# SCH_Driver_Key_PCB_3_5_3_8_5_0_2022-10-0.net
KiCad netlist of a schematic drawn in EasyEDA
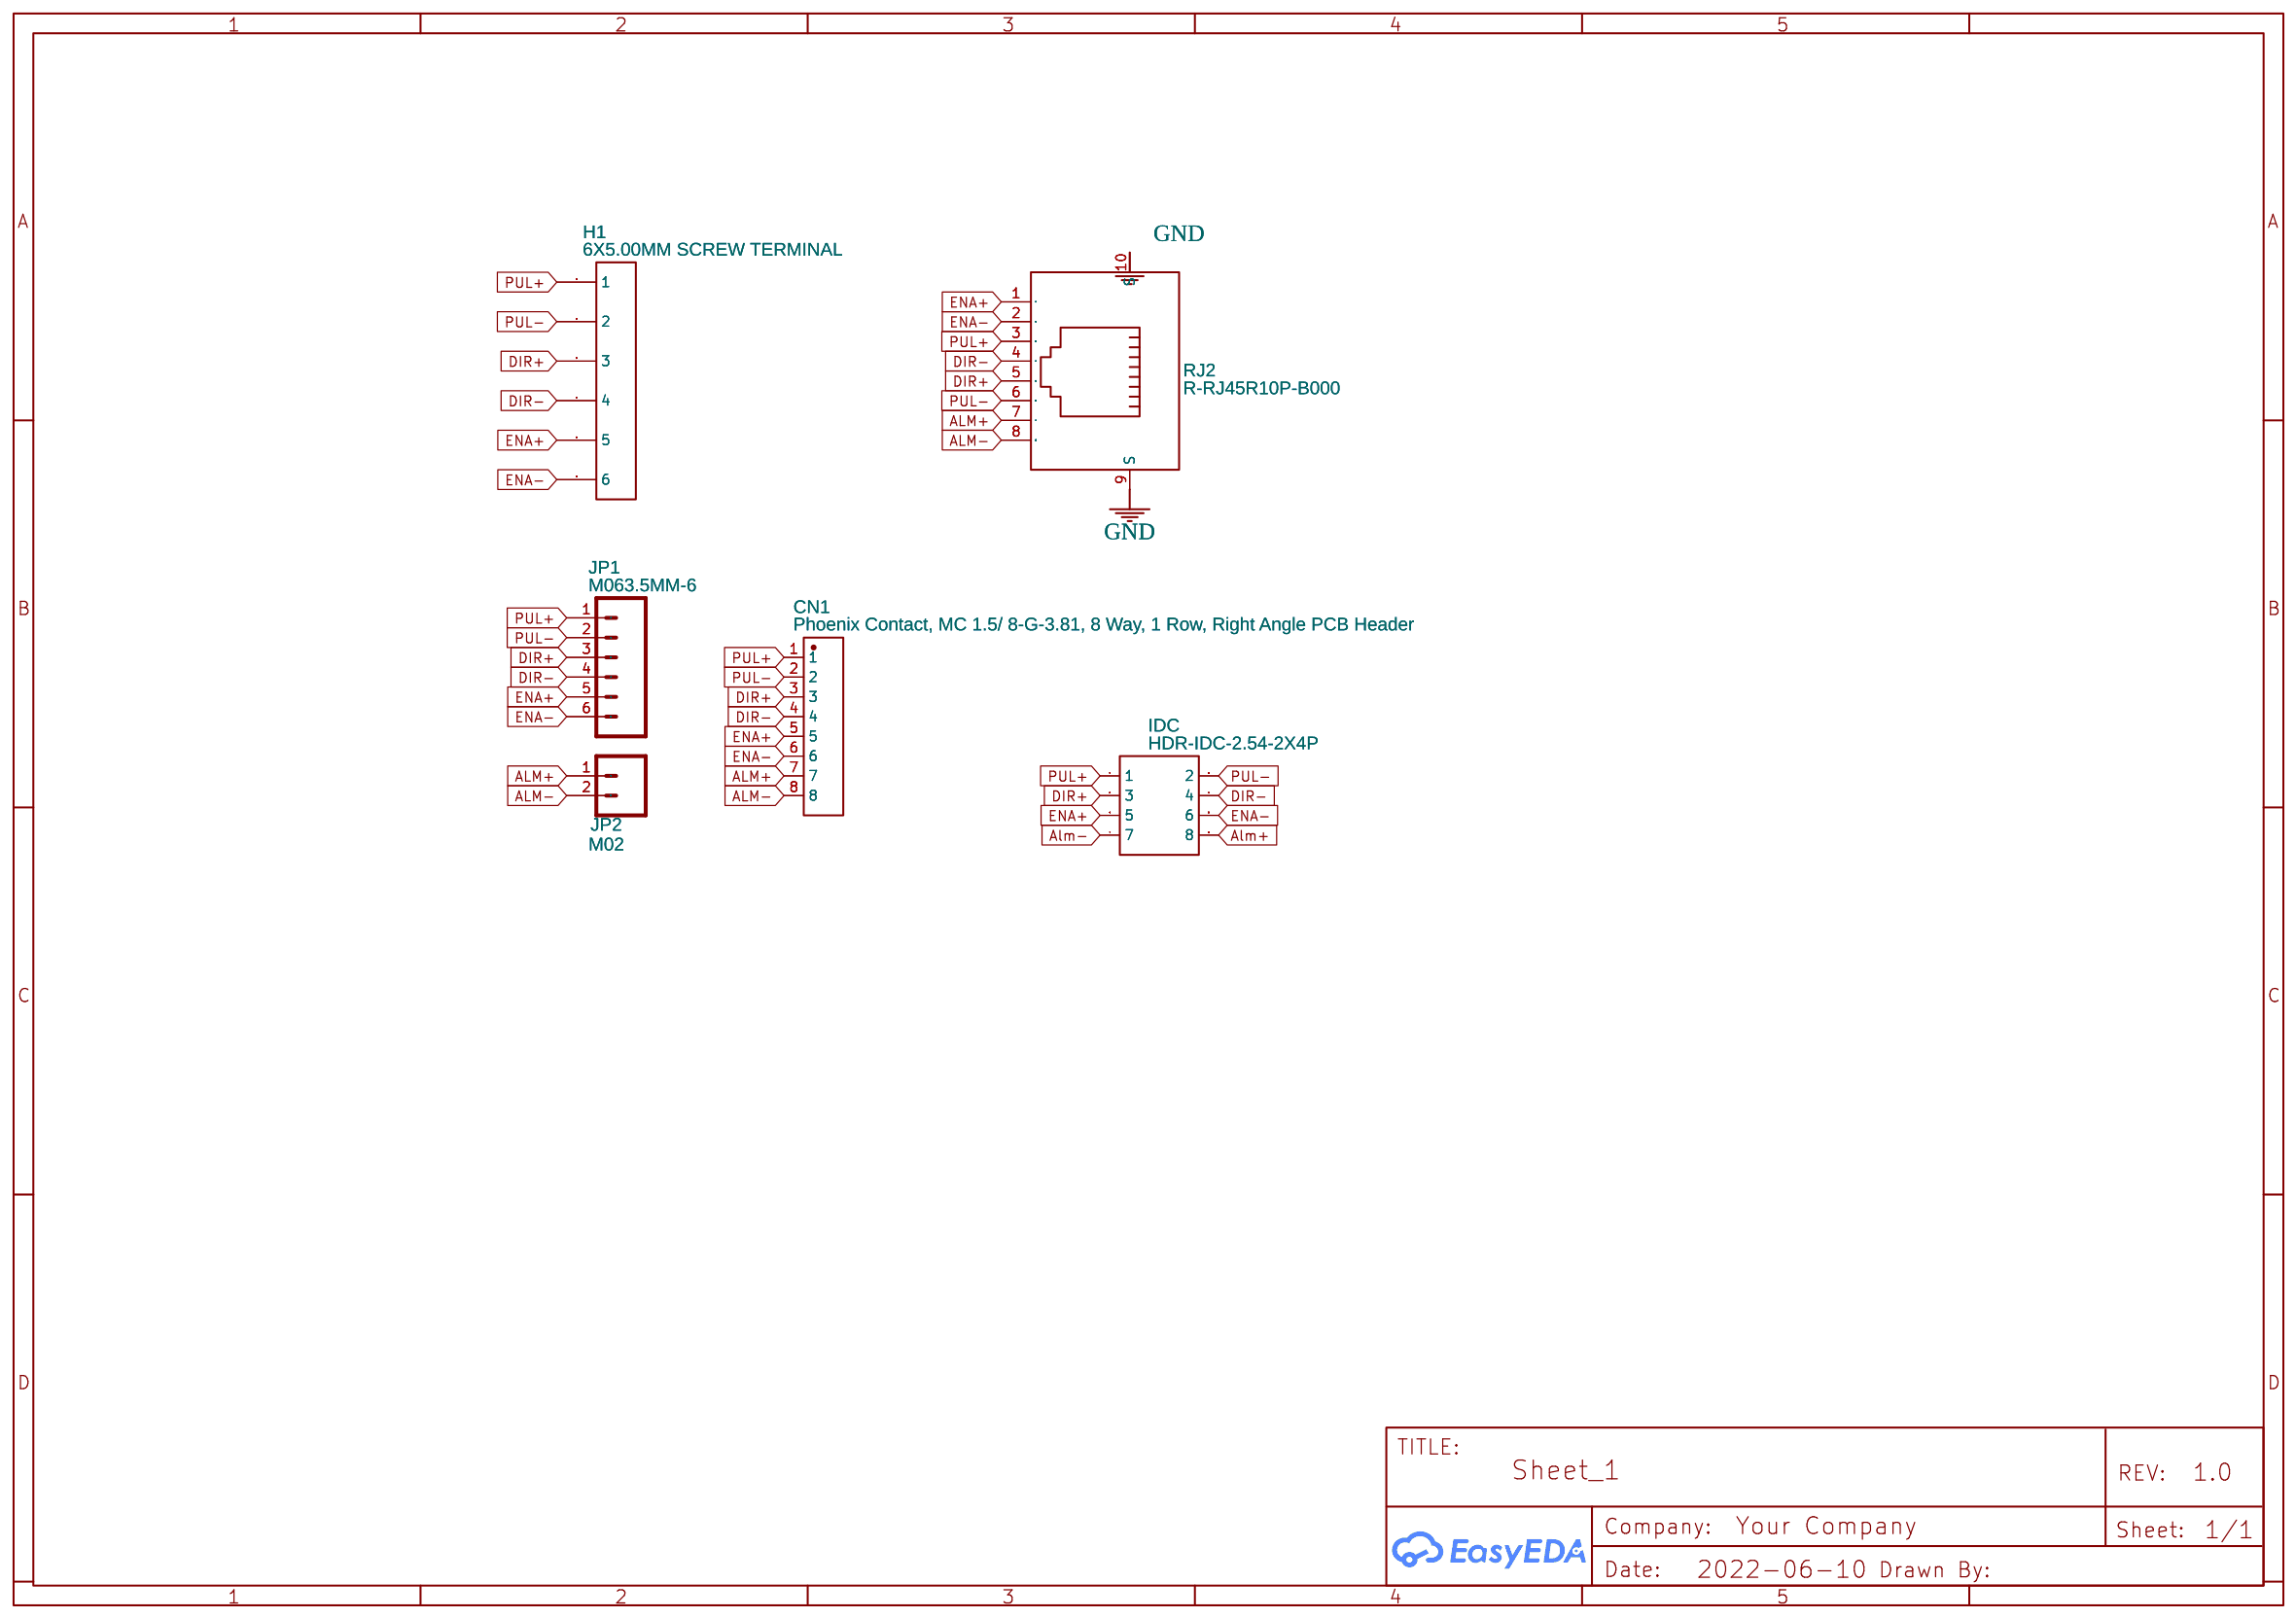
[diagram p0: schematic sheet]

(export (version "E")
  (design (tool "Eeschema 10.0.6"))
  (components
    (comp (ref "CN1")
      (value "Phoenix Contact, MC 1.5/ 8-G-3.81, 8 Way, 1 Row, Right Angle PCB Header")
      (fields (field (name "BOM_Manufacturer Part") "1803332") (field (name "BOM_Supplier Part") "220-4793"))
      (libsource (lib "") (part "Phoenix Contact, MC 1.5/ 8-G-3.81, 8 Way, 1 Row, Right Angle PCB Header"))
    )
    (comp (ref "H1") (value "6X5.00MM SCREW TERMINAL") (libsource (lib "") (part "6X5.00MM SCREW TERMINAL")))
    (comp (ref "IDC")
      (value "HDR-IDC-2.54-2X4P")
      (fields
        (field (name "BOM_Manufacturer Part") "IDC Box 2X4 2.54MM")
        (field (name "BOM_Supplier Part") "C9135")
      )
      (libsource (lib "") (part "HDR-IDC-2.54-2X4P"))
    )
    (comp (ref "JP1") (value "M063.5MM-6") (libsource (lib "") (part "M063.5MM-6")))
    (comp (ref "JP2") (value "M02") (libsource (lib "") (part "M02")))
    (comp (ref "RJ2")
      (value "R-RJ45R10P-B000")
      (fields (field (name "BOM_Supplier Part") "C386758"))
      (libsource (lib "") (part "R-RJ45R10P-B000"))
    )
  )
  (nets
    (net (code "1") (name "ALM+") (class "Default")
      (node (ref "CN1") (pin "7") (pinfunction "7_7") (pintype "unspecified"))
      (node (ref "JP2") (pin "1") (pinfunction "1_1") (pintype "unspecified"))
      (node (ref "RJ2") (pin "7") (pinfunction "7_7") (pintype "unspecified"))
    )
    (net (code "2") (name "ALM-") (class "Default")
      (node (ref "CN1") (pin "8") (pinfunction "8_8") (pintype "unspecified"))
      (node (ref "JP2") (pin "2") (pinfunction "2_2") (pintype "unspecified"))
      (node (ref "RJ2") (pin "8") (pinfunction "8_8") (pintype "unspecified"))
    )
    (net (code "3") (name "Alm+") (class "Default")
      (node (ref "IDC") (pin "8") (pinfunction "8_8") (pintype "unspecified"))
    )
    (net (code "4") (name "Alm-") (class "Default")
      (node (ref "IDC") (pin "7") (pinfunction "7_7") (pintype "unspecified"))
    )
    (net (code "5") (name "DIR+") (class "Default")
      (node (ref "CN1") (pin "3") (pinfunction "3_3") (pintype "unspecified"))
      (node (ref "H1") (pin "3") (pinfunction "3_3") (pintype "unspecified"))
      (node (ref "IDC") (pin "3") (pinfunction "3_3") (pintype "unspecified"))
      (node (ref "JP1") (pin "3") (pinfunction "3_3") (pintype "unspecified"))
      (node (ref "RJ2") (pin "5") (pinfunction "5_5") (pintype "unspecified"))
    )
    (net (code "6") (name "DIR-") (class "Default")
      (node (ref "CN1") (pin "4") (pinfunction "4_4") (pintype "unspecified"))
      (node (ref "H1") (pin "4") (pinfunction "4_4") (pintype "unspecified"))
      (node (ref "IDC") (pin "4") (pinfunction "4_4") (pintype "unspecified"))
      (node (ref "JP1") (pin "4") (pinfunction "4_4") (pintype "unspecified"))
      (node (ref "RJ2") (pin "4") (pinfunction "4_4") (pintype "unspecified"))
    )
    (net (code "7") (name "ENA+") (class "Default")
      (node (ref "CN1") (pin "5") (pinfunction "5_5") (pintype "unspecified"))
      (node (ref "H1") (pin "5") (pinfunction "5_5") (pintype "unspecified"))
      (node (ref "IDC") (pin "5") (pinfunction "5_5") (pintype "unspecified"))
      (node (ref "JP1") (pin "5") (pinfunction "5_5") (pintype "unspecified"))
      (node (ref "RJ2") (pin "1") (pinfunction "1_1") (pintype "unspecified"))
    )
    (net (code "8") (name "ENA-") (class "Default")
      (node (ref "CN1") (pin "6") (pinfunction "6_6") (pintype "unspecified"))
      (node (ref "H1") (pin "6") (pinfunction "6_6") (pintype "unspecified"))
      (node (ref "IDC") (pin "6") (pinfunction "6_6") (pintype "unspecified"))
      (node (ref "JP1") (pin "6") (pinfunction "6_6") (pintype "unspecified"))
      (node (ref "RJ2") (pin "2") (pinfunction "2_2") (pintype "unspecified"))
    )
    (net (code "9") (name "GND") (class "Default")
      (node (ref "RJ2") (pin "10") (pinfunction "S_10") (pintype "unspecified"))
      (node (ref "RJ2") (pin "9") (pinfunction "S_9") (pintype "unspecified"))
    )
    (net (code "10") (name "PUL+") (class "Default")
      (node (ref "CN1") (pin "1") (pinfunction "1_1") (pintype "unspecified"))
      (node (ref "H1") (pin "1") (pinfunction "1_1") (pintype "unspecified"))
      (node (ref "IDC") (pin "1") (pinfunction "1_1") (pintype "unspecified"))
      (node (ref "JP1") (pin "1") (pinfunction "1_1") (pintype "unspecified"))
      (node (ref "RJ2") (pin "3") (pinfunction "3_3") (pintype "unspecified"))
    )
    (net (code "11") (name "PUL-") (class "Default")
      (node (ref "CN1") (pin "2") (pinfunction "2_2") (pintype "unspecified"))
      (node (ref "H1") (pin "2") (pinfunction "2_2") (pintype "unspecified"))
      (node (ref "IDC") (pin "2") (pinfunction "2_2") (pintype "unspecified"))
      (node (ref "JP1") (pin "2") (pinfunction "2_2") (pintype "unspecified"))
      (node (ref "RJ2") (pin "6") (pinfunction "6_6") (pintype "unspecified"))
    )
  )
)
